# Dual_PressureSensor_DLC_v1_1_mrt2022.net
KiCad netlist of a schematic drawn in EAGLE
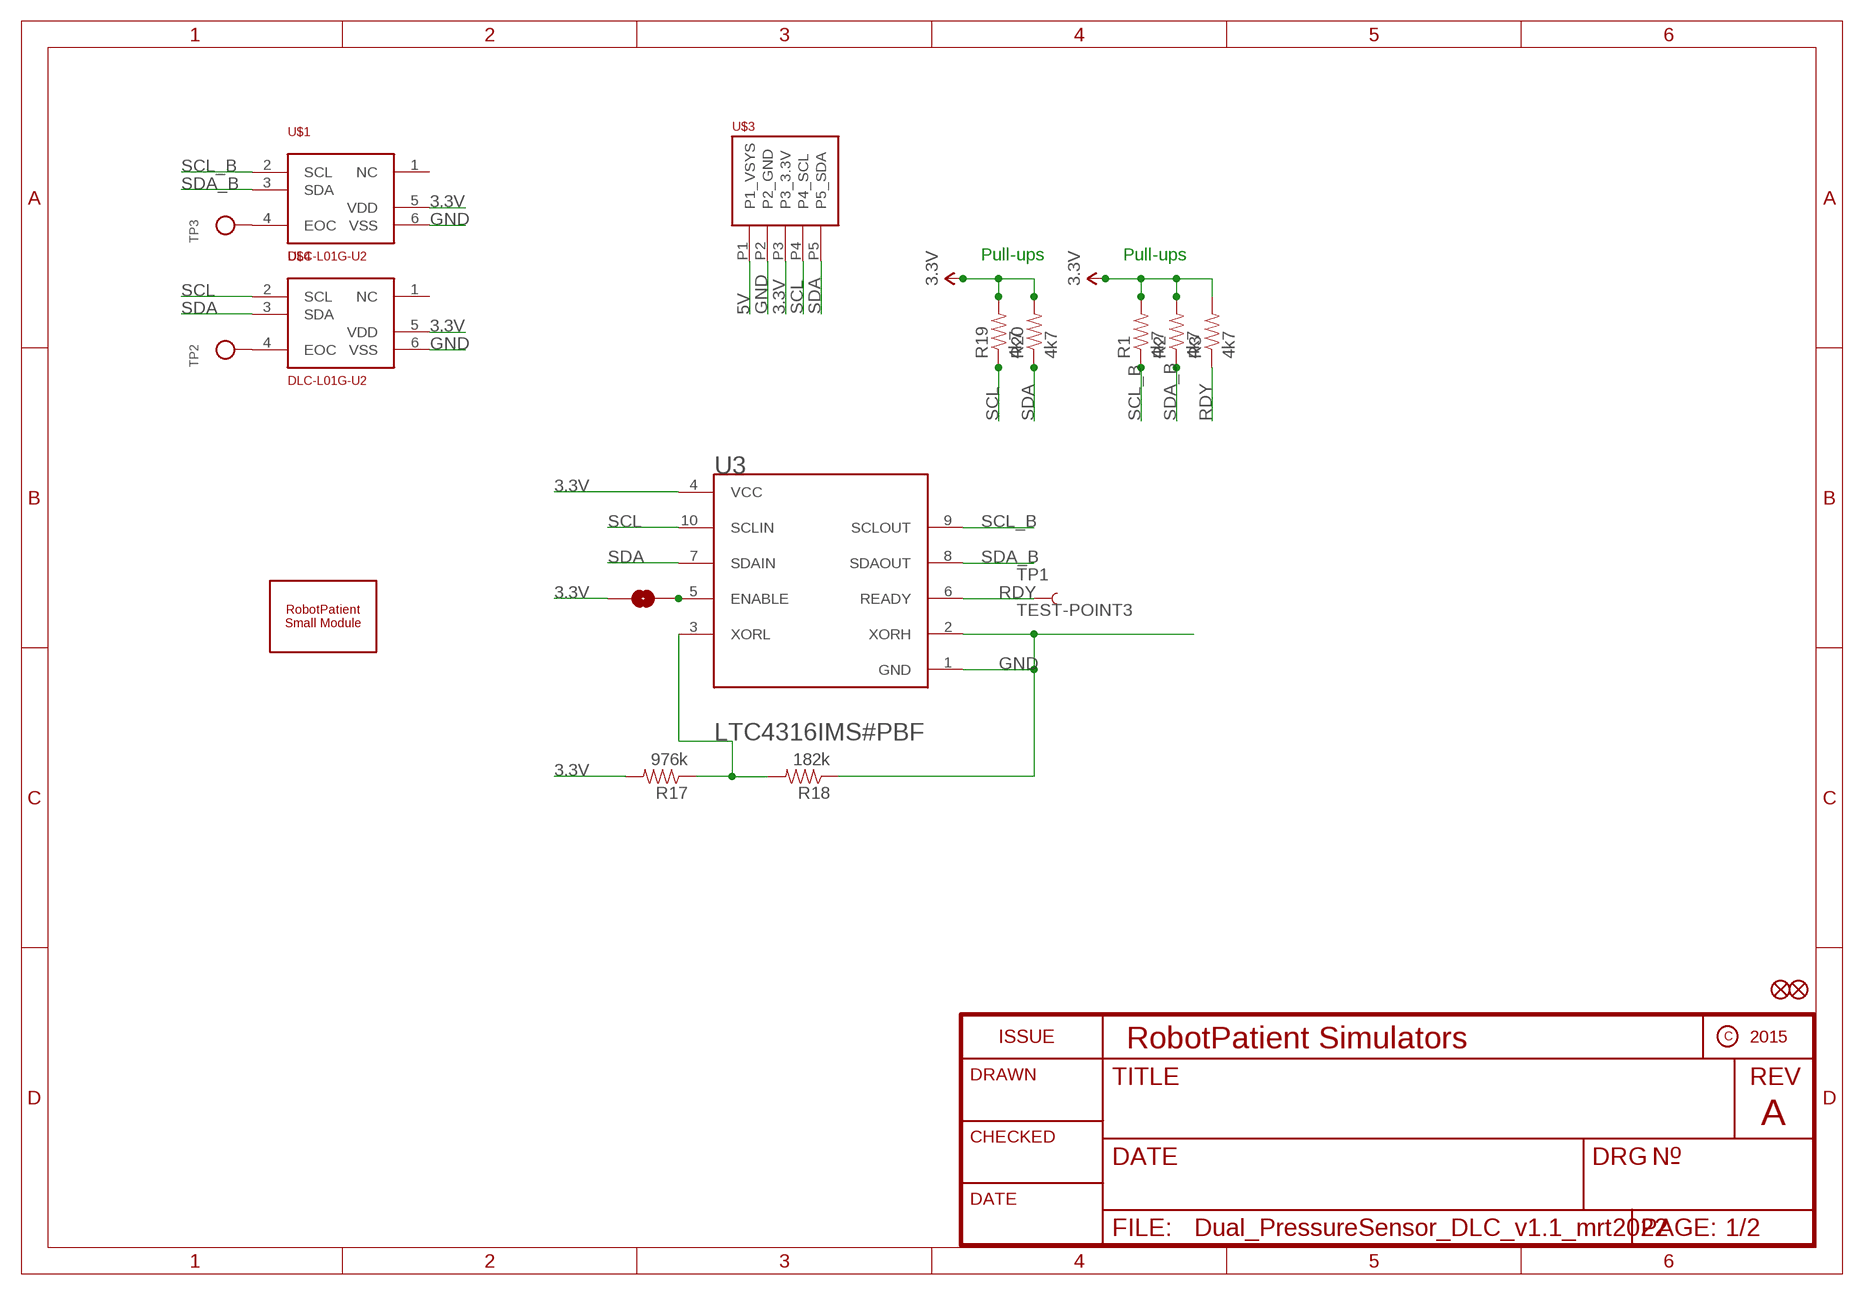
[diagram p0: schematic, sheet 1]
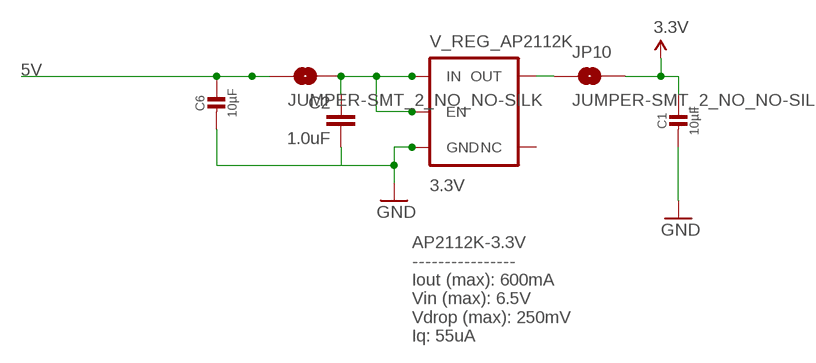
[diagram p1: schematic, sheet 2]

(export (version "E")
  (design (tool "Eeschema 10.0.6"))
  (components
    (comp (ref "C1")
      (value "10µF")
      (footprint "eagle-import:0805-NO")
      (libsource (lib "eagle-import") (part "CAP_CERAMIC0805-NOOUTLINE"))
    )
    (comp (ref "C2")
      (value "1.0uF")
      (footprint "eagle-import:0805-CAP")
      (libsource (lib "eagle-import") (part "1.0UF-25V-+80/-20(0805){dblquote}"))
    )
    (comp (ref "C6")
      (value "10µF")
      (footprint "eagle-import:0805-NO")
      (libsource (lib "eagle-import") (part "CAP_CERAMIC0805-NOOUTLINE"))
    )
    (comp (ref "JP10")
      (value "JUMPER-SMT_2_NO_NO-SILK")
      (footprint "eagle-import:SMT-JUMPER_2_NO_NO-SILK")
      (libsource (lib "eagle-import") (part "JUMPER-SMT_2_NO_NO-SILK"))
    )
    (comp (ref "JP11")
      (value "JUMPER-SMT_2_NO_NO-SILK")
      (footprint "eagle-import:SMT-JUMPER_2_NO_NO-SILK")
      (libsource (lib "eagle-import") (part "JUMPER-SMT_2_NO_NO-SILK"))
    )
    (comp (ref "V_REG_AP2112K")
      (value "3.3V")
      (footprint "eagle-import:SOT23-5")
      (libsource (lib "eagle-import") (part "V_REG_AP2112K-3.3V"))
    )
    (comp (ref "FID1")
      (value "FIDUCIAL\"\"")
      (footprint "eagle-import:FIDUCIAL_1MM")
      (libsource (lib "eagle-import") (part "FIDUCIAL{dblquote}{dblquote}"))
    )
    (comp (ref "FID2")
      (value "FIDUCIAL\"\"")
      (footprint "eagle-import:FIDUCIAL_1MM")
      (libsource (lib "eagle-import") (part "FIDUCIAL{dblquote}{dblquote}"))
    )
    (comp (ref "JP3")
      (value "JUMPER-SMT_2_NO_NO-SILK")
      (footprint "eagle-import:SMT-JUMPER_2_NO_NO-SILK")
      (libsource (lib "eagle-import") (part "JUMPER-SMT_2_NO_NO-SILK"))
    )
    (comp (ref "R1")
      (value "4k7")
      (footprint "eagle-import:0603-RES")
      (libsource (lib "eagle-import") (part "47KOHM1/10W1%(0603)"))
    )
    (comp (ref "R2")
      (value "4k7")
      (footprint "eagle-import:0603-RES")
      (libsource (lib "eagle-import") (part "47KOHM1/10W1%(0603)"))
    )
    (comp (ref "R3")
      (value "4k7")
      (footprint "eagle-import:0603-RES")
      (libsource (lib "eagle-import") (part "47KOHM1/10W1%(0603)"))
    )
    (comp (ref "R17")
      (value "976k")
      (footprint "eagle-import:0603-RES")
      (libsource (lib "eagle-import") (part "47KOHM1/10W1%(0603)"))
    )
    (comp (ref "R18")
      (value "182k")
      (footprint "eagle-import:0603-RES")
      (libsource (lib "eagle-import") (part "47KOHM1/10W1%(0603)"))
    )
    (comp (ref "R19")
      (value "4k7")
      (footprint "eagle-import:0603-RES")
      (libsource (lib "eagle-import") (part "47KOHM1/10W1%(0603)"))
    )
    (comp (ref "R20")
      (value "4k7")
      (footprint "eagle-import:0603-RES")
      (libsource (lib "eagle-import") (part "47KOHM1/10W1%(0603)"))
    )
    (comp (ref "TP1")
      (value "TEST-POINT3")
      (footprint "eagle-import:PAD.03X.03")
      (libsource (lib "eagle-import") (part "TEST-POINT3"))
    )
    (comp (ref "TP2")
      (value "TESTPOINTROUND1MM")
      (footprint "eagle-import:TESTPOINT_ROUND_1MM")
      (libsource (lib "eagle-import") (part "TESTPOINTROUND1MM"))
    )
    (comp (ref "TP3")
      (value "TESTPOINTROUND1MM")
      (footprint "eagle-import:TESTPOINT_ROUND_1MM")
      (libsource (lib "eagle-import") (part "TESTPOINTROUND1MM"))
    )
    (comp (ref "U$1")
      (value "DLC-L01G-U2")
      (footprint "eagle-import:DLC-L01G-U2")
      (libsource (lib "eagle-import") (part "DLC-L01G-U2"))
    )
    (comp (ref "U$2")
      (value "ROBOTPATIENT_SMALL_MODULEBOARD")
      (footprint "eagle-import:RP_SMALL_SENSOR_OUTLINE")
      (libsource (lib "eagle-import") (part "ROBOTPATIENT_SMALL_MODULEBOARD"))
    )
    (comp (ref "U$3")
      (value "PHOENIX_PTSM_M5_TH_I2C++")
      (footprint "eagle-import:PTSM_M5_THRHOLE")
      (libsource (lib "eagle-import") (part "PHOENIX_PTSM_M5_TH_I2C++"))
    )
    (comp (ref "U$4")
      (value "DLC-L01G-U2")
      (footprint "eagle-import:DLC-L01G-U2")
      (libsource (lib "eagle-import") (part "DLC-L01G-U2"))
    )
    (comp (ref "U3")
      (value "ANALOG_DEVICES_LTC4316IMS#PBFANALOG_DEVICES_LTC4316IMS#PBF_0_0")
      (footprint "eagle-import:ANALOG_DEVICES_LTC4316IMS#PBF_0")
      (fields
        (field (name "DIGIKEY_PART_NUMBER") "LTC4316IMS#PBF-ND")
        (field (name "MF") "Analog Devices")
        (field (name "MOUSER_PART_NUMBER") "584-LTC4316IMS#PBF")
      )
      (libsource (lib "eagle-import") (part "ANALOG_DEVICES_LTC4316IMS#PBFANALOG_DEVICES_LTC4316IMS#PBF_0_0"))
    )
  )
  (nets
    (net (code "1") (name "3.3V") (class "Default")
      (node (ref "C1") (pin "1") (pinfunction "1_1") (pintype "passive"))
      (node (ref "JP10") (pin "2") (pinfunction "2_2") (pintype "passive"))
      (node (ref "JP3") (pin "1") (pinfunction "1_1") (pintype "passive"))
      (node (ref "R1") (pin "2") (pinfunction "2_2") (pintype "passive"))
      (node (ref "R17") (pin "2") (pinfunction "2_2") (pintype "passive"))
      (node (ref "R19") (pin "2") (pinfunction "2_2") (pintype "passive"))
      (node (ref "R2") (pin "2") (pinfunction "2_2") (pintype "passive"))
      (node (ref "R20") (pin "2") (pinfunction "2_2") (pintype "passive"))
      (node (ref "R3") (pin "2") (pinfunction "2_2") (pintype "passive"))
      (node (ref "U$1") (pin "5") (pinfunction "VDD_5") (pintype "bidirectional"))
      (node (ref "U$3") (pin "P3") (pinfunction "P3_3.3V_P3") (pintype "power_in"))
      (node (ref "U$4") (pin "5") (pinfunction "VDD_5") (pintype "bidirectional"))
      (node (ref "U3") (pin "4") (pinfunction "VCC_4") (pintype "power_in"))
    )
    (net (code "2") (name "5V") (class "Default")
      (node (ref "C6") (pin "1") (pinfunction "1_1") (pintype "passive"))
      (node (ref "JP11") (pin "1") (pinfunction "1_1") (pintype "passive"))
      (node (ref "U$3") (pin "P1") (pinfunction "P1_VSYS_P1") (pintype "power_in"))
    )
    (net (code "3") (name "GND") (class "Default")
      (node (ref "C1") (pin "2") (pinfunction "2_2") (pintype "passive"))
      (node (ref "C2") (pin "2") (pinfunction "2_2") (pintype "passive"))
      (node (ref "C6") (pin "2") (pinfunction "2_2") (pintype "passive"))
      (node (ref "R18") (pin "1") (pinfunction "1_1") (pintype "passive"))
      (node (ref "U$1") (pin "6") (pinfunction "VSS_6") (pintype "bidirectional"))
      (node (ref "U$3") (pin "P2") (pinfunction "P2_GND_P2") (pintype "power_in"))
      (node (ref "U$4") (pin "6") (pinfunction "VSS_6") (pintype "bidirectional"))
      (node (ref "U3") (pin "1") (pinfunction "GND_1") (pintype "power_in"))
      (node (ref "U3") (pin "2") (pinfunction "XORH_2") (pintype "passive"))
      (node (ref "V_REG_AP2112K") (pin "2") (pinfunction "GND_2") (pintype "input"))
    )
    (net (code "4") (name "Net-(U$1-EOC)") (class "Default")
      (node (ref "TP3") (pin "P$1") (pinfunction "P$1_P$1") (pintype "bidirectional"))
      (node (ref "U$1") (pin "4") (pinfunction "EOC_4") (pintype "bidirectional"))
    )
    (net (code "5") (name "Net-(U$4-EOC)") (class "Default")
      (node (ref "TP2") (pin "P$1") (pinfunction "P$1_P$1") (pintype "bidirectional"))
      (node (ref "U$4") (pin "4") (pinfunction "EOC_4") (pintype "bidirectional"))
    )
    (net (code "6") (name "Net-(U3-ENABLE)") (class "Default")
      (node (ref "JP3") (pin "2") (pinfunction "2_2") (pintype "passive"))
      (node (ref "U3") (pin "5") (pinfunction "ENABLE_5") (pintype "input"))
    )
    (net (code "7") (name "Net-(U3-XORL)") (class "Default")
      (node (ref "R17") (pin "1") (pinfunction "1_1") (pintype "passive"))
      (node (ref "R18") (pin "2") (pinfunction "2_2") (pintype "passive"))
      (node (ref "U3") (pin "3") (pinfunction "XORL_3") (pintype "passive"))
    )
    (net (code "8") (name "Net-(V_REG_AP2112K-EN)") (class "Default")
      (node (ref "C2") (pin "1") (pinfunction "1_1") (pintype "passive"))
      (node (ref "JP11") (pin "2") (pinfunction "2_2") (pintype "passive"))
      (node (ref "V_REG_AP2112K") (pin "1") (pinfunction "IN_1") (pintype "input"))
      (node (ref "V_REG_AP2112K") (pin "3") (pinfunction "EN_3") (pintype "input"))
    )
    (net (code "9") (name "Net-(V_REG_AP2112K-OUT)") (class "Default")
      (node (ref "JP10") (pin "1") (pinfunction "1_1") (pintype "passive"))
      (node (ref "V_REG_AP2112K") (pin "5") (pinfunction "OUT_5") (pintype "passive"))
    )
    (net (code "10") (name "RDY") (class "Default")
      (node (ref "R3") (pin "1") (pinfunction "1_1") (pintype "passive"))
      (node (ref "TP1") (pin "P$1") (pinfunction "1_P$1") (pintype "bidirectional"))
      (node (ref "U3") (pin "6") (pinfunction "READY_6") (pintype "output"))
    )
    (net (code "11") (name "SCL") (class "Default")
      (node (ref "R19") (pin "1") (pinfunction "1_1") (pintype "passive"))
      (node (ref "U$3") (pin "P4") (pinfunction "P4_SCL_P4") (pintype "bidirectional"))
      (node (ref "U$4") (pin "2") (pinfunction "SCL_2") (pintype "bidirectional"))
      (node (ref "U3") (pin "10") (pinfunction "SCLIN_10") (pintype "input"))
    )
    (net (code "12") (name "SCL_B") (class "Default")
      (node (ref "R1") (pin "1") (pinfunction "1_1") (pintype "passive"))
      (node (ref "U$1") (pin "2") (pinfunction "SCL_2") (pintype "bidirectional"))
      (node (ref "U3") (pin "9") (pinfunction "SCLOUT_9") (pintype "output"))
    )
    (net (code "13") (name "SDA") (class "Default")
      (node (ref "R20") (pin "1") (pinfunction "1_1") (pintype "passive"))
      (node (ref "U$3") (pin "P5") (pinfunction "P5_SDA_P5") (pintype "bidirectional"))
      (node (ref "U$4") (pin "3") (pinfunction "SDA_3") (pintype "bidirectional"))
      (node (ref "U3") (pin "7") (pinfunction "SDAIN_7") (pintype "input"))
    )
    (net (code "14") (name "SDA_B") (class "Default")
      (node (ref "R2") (pin "1") (pinfunction "1_1") (pintype "passive"))
      (node (ref "U$1") (pin "3") (pinfunction "SDA_3") (pintype "bidirectional"))
      (node (ref "U3") (pin "8") (pinfunction "SDAOUT_8") (pintype "output"))
    )
    (net (code "15") (name "unconnected-(U$1-NC-Pad1)") (class "Default")
      (node (ref "U$1") (pin "1") (pinfunction "NC_1") (pintype "bidirectional"))
    )
    (net (code "16") (name "unconnected-(U$4-NC-Pad1)") (class "Default")
      (node (ref "U$4") (pin "1") (pinfunction "NC_1") (pintype "bidirectional"))
    )
    (net (code "17") (name "unconnected-(V_REG_AP2112K-NC-Pad4)") (class "Default")
      (node (ref "V_REG_AP2112K") (pin "4") (pinfunction "NC_4") (pintype "input"))
    )
  )
)
